# knowles_mic_v2.net
KiCad netlist of a schematic drawn in EAGLE
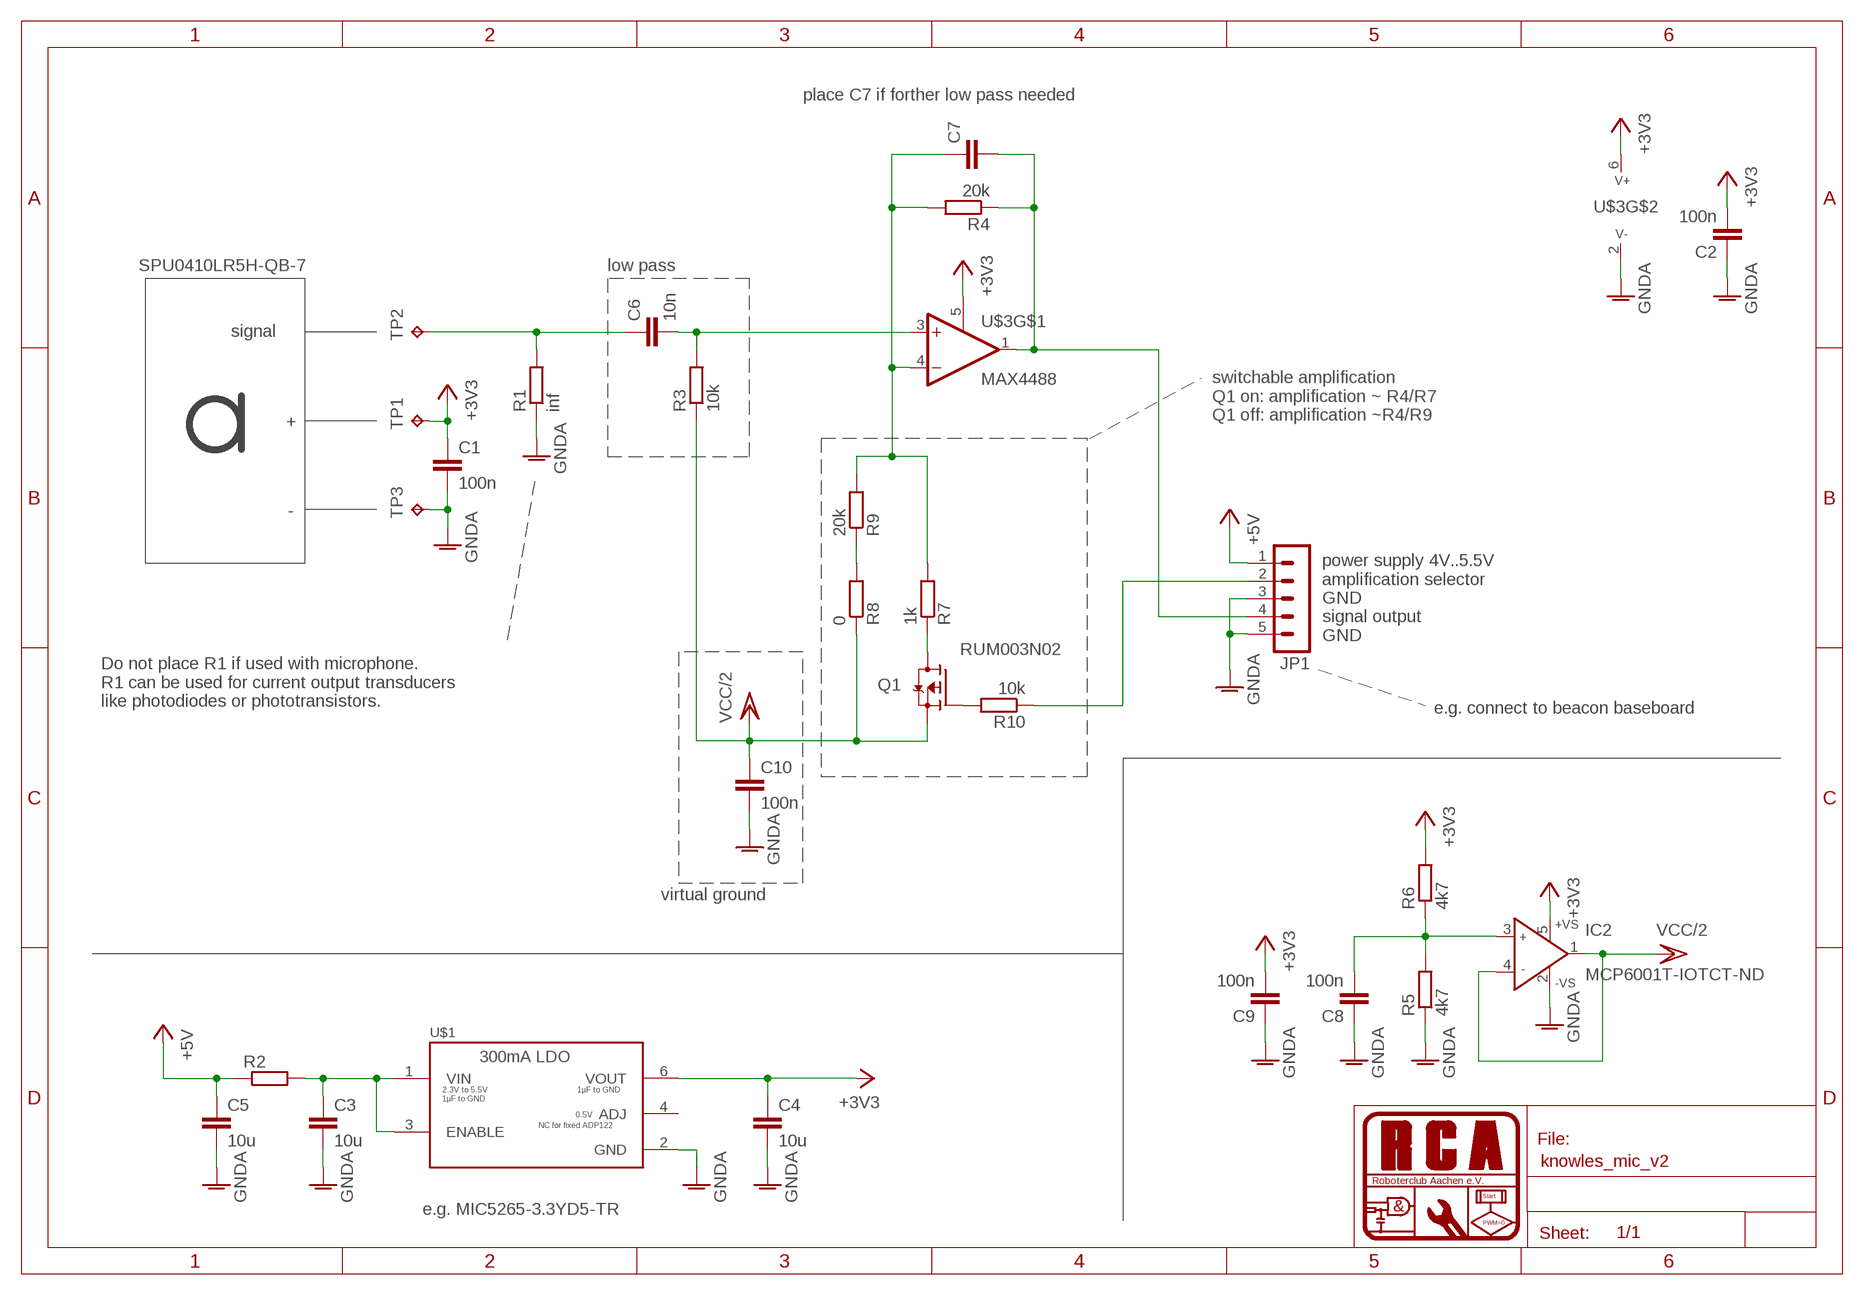
[diagram p0: schematic, sheet 1]

(export (version "E")
  (design (tool "Eeschema 10.0.6"))
  (components
    (comp (ref "C1")
      (value "100n")
      (footprint "eagle-import:C0603")
      (libsource (lib "eagle-import") (part "C-EUC0603"))
    )
    (comp (ref "C2")
      (value "100n")
      (footprint "eagle-import:C0603")
      (libsource (lib "eagle-import") (part "C-EUC0603"))
    )
    (comp (ref "C3")
      (value "10u")
      (footprint "eagle-import:C0805")
      (libsource (lib "eagle-import") (part "C-EUC0805"))
    )
    (comp (ref "C4")
      (value "10u")
      (footprint "eagle-import:C0805")
      (libsource (lib "eagle-import") (part "C-EUC0805"))
    )
    (comp (ref "C5")
      (value "10u")
      (footprint "eagle-import:C0805")
      (libsource (lib "eagle-import") (part "C-EUC0805"))
    )
    (comp (ref "C6")
      (value "10n")
      (footprint "eagle-import:C0603")
      (libsource (lib "eagle-import") (part "C-EUC0603"))
    )
    (comp (ref "C7")
      (value "C-EUC0603")
      (footprint "eagle-import:C0603")
      (libsource (lib "eagle-import") (part "C-EUC0603"))
    )
    (comp (ref "C8")
      (value "100n")
      (footprint "eagle-import:C0603")
      (libsource (lib "eagle-import") (part "C-EUC0603"))
    )
    (comp (ref "C9")
      (value "100n")
      (footprint "eagle-import:C0603")
      (libsource (lib "eagle-import") (part "C-EUC0603"))
    )
    (comp (ref "C10")
      (value "100n")
      (footprint "eagle-import:C0603")
      (libsource (lib "eagle-import") (part "C-EUC0603"))
    )
    (comp (ref "IC2")
      (value "MCP6001T-IOTCT-ND")
      (footprint "eagle-import:SOT23-5")
      (fields (field (name "MF") "ALTERA CORPORATION") (field (name "MPN") "AD8519ARTZ-REEL7"))
      (libsource (lib "eagle-import") (part "AD8519RJ"))
    )
    (comp (ref "JP1")
      (value "PSS_5G")
      (footprint "eagle-import:22-23-2051")
      (libsource (lib "eagle-import") (part "PSS_5G"))
    )
    (comp (ref "Q1")
      (value "RUM003N02")
      (footprint "eagle-import:SC75_INFINEON")
      (libsource (lib "eagle-import") (part "BSA223SP"))
    )
    (comp (ref "R1")
      (value "inf")
      (footprint "eagle-import:R0603")
      (libsource (lib "eagle-import") (part "R-EU_R0603"))
    )
    (comp (ref "R2")
      (value "R-EU_R0603")
      (footprint "eagle-import:R0603")
      (libsource (lib "eagle-import") (part "R-EU_R0603"))
    )
    (comp (ref "R3")
      (value "10k")
      (footprint "eagle-import:R0603")
      (libsource (lib "eagle-import") (part "R-EU_R0603"))
    )
    (comp (ref "R4")
      (value "20k")
      (footprint "eagle-import:R0603")
      (libsource (lib "eagle-import") (part "R-EU_R0603"))
    )
    (comp (ref "R5")
      (value "4k7")
      (footprint "eagle-import:R0603")
      (libsource (lib "eagle-import") (part "R-EU_R0603"))
    )
    (comp (ref "R6")
      (value "4k7")
      (footprint "eagle-import:R0603")
      (libsource (lib "eagle-import") (part "R-EU_R0603"))
    )
    (comp (ref "R7")
      (value "1k")
      (footprint "eagle-import:R0603")
      (libsource (lib "eagle-import") (part "R-EU_R0603"))
    )
    (comp (ref "R8")
      (value "0")
      (footprint "eagle-import:R0603")
      (libsource (lib "eagle-import") (part "R-EU_R0603"))
    )
    (comp (ref "R9")
      (value "20k")
      (footprint "eagle-import:R0603")
      (libsource (lib "eagle-import") (part "R-EU_R0603"))
    )
    (comp (ref "R10")
      (value "10k")
      (footprint "eagle-import:R0603")
      (libsource (lib "eagle-import") (part "R-EU_R0603"))
    )
    (comp (ref "TP1")
      (value "TPTP06R")
      (footprint "eagle-import:TP06R")
      (libsource (lib "eagle-import") (part "TPTP06R"))
    )
    (comp (ref "TP2")
      (value "TPTP06R")
      (footprint "eagle-import:TP06R")
      (libsource (lib "eagle-import") (part "TPTP06R"))
    )
    (comp (ref "TP3")
      (value "TPTP06R")
      (footprint "eagle-import:TP06R")
      (libsource (lib "eagle-import") (part "TPTP06R"))
    )
    (comp (ref "U$1")
      (value "ADP123")
      (footprint "eagle-import:TSOT23-6")
      (libsource (lib "eagle-import") (part "ADP123"))
    )
    (comp (ref "U$3")
      (value "MAX4488")
      (footprint "eagle-import:TSOT23-6")
      (libsource (lib "eagle-import") (part "MAX4488"))
    )
  )
  (nets
    (net (code "1") (name "+3V3") (class "Default")
      (node (ref "C1") (pin "1") (pinfunction "1_1") (pintype "passive"))
      (node (ref "C2") (pin "2") (pinfunction "2_2") (pintype "passive"))
      (node (ref "C4") (pin "1") (pinfunction "1_1") (pintype "passive"))
      (node (ref "C9") (pin "2") (pinfunction "2_2") (pintype "passive"))
      (node (ref "IC2") (pin "5") (pinfunction "+VS_5") (pintype "input"))
      (node (ref "R6") (pin "2") (pinfunction "2_2") (pintype "passive"))
      (node (ref "TP1") (pin "TP") (pinfunction "TP_TP") (pintype "input"))
      (node (ref "U$1") (pin "6") (pinfunction "VOUT_6") (pintype "bidirectional"))
      (node (ref "U$3") (pin "5") (pinfunction "EN_5") (pintype "input"))
      (node (ref "U$3") (pin "6") (pinfunction "V+_6") (pintype "power_in"))
    )
    (net (code "2") (name "+5V") (class "Default")
      (node (ref "C5") (pin "1") (pinfunction "1_1") (pintype "passive"))
      (node (ref "JP1") (pin "1") (pinfunction "1_1") (pintype "passive"))
      (node (ref "R2") (pin "1") (pinfunction "1_1") (pintype "passive"))
    )
    (net (code "3") (name "GNDA") (class "Default")
      (node (ref "C1") (pin "2") (pinfunction "2_2") (pintype "passive"))
      (node (ref "C10") (pin "2") (pinfunction "2_2") (pintype "passive"))
      (node (ref "C2") (pin "1") (pinfunction "1_1") (pintype "passive"))
      (node (ref "C3") (pin "2") (pinfunction "2_2") (pintype "passive"))
      (node (ref "C4") (pin "2") (pinfunction "2_2") (pintype "passive"))
      (node (ref "C5") (pin "2") (pinfunction "2_2") (pintype "passive"))
      (node (ref "C8") (pin "1") (pinfunction "1_1") (pintype "passive"))
      (node (ref "C9") (pin "1") (pinfunction "1_1") (pintype "passive"))
      (node (ref "IC2") (pin "2") (pinfunction "-VS_2") (pintype "input"))
      (node (ref "JP1") (pin "3") (pinfunction "3_3") (pintype "passive"))
      (node (ref "JP1") (pin "5") (pinfunction "5_5") (pintype "passive"))
      (node (ref "R1") (pin "1") (pinfunction "1_1") (pintype "passive"))
      (node (ref "R5") (pin "1") (pinfunction "1_1") (pintype "passive"))
      (node (ref "TP3") (pin "TP") (pinfunction "TP_TP") (pintype "input"))
      (node (ref "U$1") (pin "2") (pinfunction "GND_2") (pintype "bidirectional"))
      (node (ref "U$3") (pin "2") (pinfunction "V-_2") (pintype "power_in"))
    )
    (net (code "4") (name "Net-(C6-Pad1)") (class "Default")
      (node (ref "C6") (pin "1") (pinfunction "1_1") (pintype "passive"))
      (node (ref "R1") (pin "2") (pinfunction "2_2") (pintype "passive"))
      (node (ref "TP2") (pin "TP") (pinfunction "TP_TP") (pintype "input"))
    )
    (net (code "5") (name "Net-(IC2-IN+)") (class "Default")
      (node (ref "C8") (pin "2") (pinfunction "2_2") (pintype "passive"))
      (node (ref "IC2") (pin "3") (pinfunction "IN+_3") (pintype "input"))
      (node (ref "R5") (pin "2") (pinfunction "2_2") (pintype "passive"))
      (node (ref "R6") (pin "1") (pinfunction "1_1") (pintype "passive"))
    )
    (net (code "6") (name "Net-(JP1-Pad2)") (class "Default")
      (node (ref "JP1") (pin "2") (pinfunction "2_2") (pintype "passive"))
      (node (ref "R10") (pin "1") (pinfunction "1_1") (pintype "passive"))
    )
    (net (code "7") (name "Net-(Q1-D)") (class "Default")
      (node (ref "Q1") (pin "2") (pinfunction "D_2") (pintype "passive"))
      (node (ref "R7") (pin "1") (pinfunction "1_1") (pintype "passive"))
    )
    (net (code "8") (name "Net-(Q1-G)") (class "Default")
      (node (ref "Q1") (pin "1") (pinfunction "G_1") (pintype "passive"))
      (node (ref "R10") (pin "2") (pinfunction "2_2") (pintype "passive"))
    )
    (net (code "9") (name "Net-(R8-Pad2)") (class "Default")
      (node (ref "R8") (pin "2") (pinfunction "2_2") (pintype "passive"))
      (node (ref "R9") (pin "1") (pinfunction "1_1") (pintype "passive"))
    )
    (net (code "10") (name "Net-(U$1-ENABLE)") (class "Default")
      (node (ref "C3") (pin "1") (pinfunction "1_1") (pintype "passive"))
      (node (ref "R2") (pin "2") (pinfunction "2_2") (pintype "passive"))
      (node (ref "U$1") (pin "1") (pinfunction "VIN_1") (pintype "bidirectional"))
      (node (ref "U$1") (pin "3") (pinfunction "ENABLE_3") (pintype "bidirectional"))
    )
    (net (code "11") (name "Net-(U$3A-+IN)") (class "Default")
      (node (ref "C6") (pin "2") (pinfunction "2_2") (pintype "passive"))
      (node (ref "R3") (pin "2") (pinfunction "2_2") (pintype "passive"))
      (node (ref "U$3") (pin "3") (pinfunction "+IN_3") (pintype "input"))
    )
    (net (code "12") (name "Net-(U$3A--IN)") (class "Default")
      (node (ref "C7") (pin "1") (pinfunction "1_1") (pintype "passive"))
      (node (ref "R4") (pin "2") (pinfunction "2_2") (pintype "passive"))
      (node (ref "R7") (pin "2") (pinfunction "2_2") (pintype "passive"))
      (node (ref "R9") (pin "2") (pinfunction "2_2") (pintype "passive"))
      (node (ref "U$3") (pin "4") (pinfunction "-IN_4") (pintype "input"))
    )
    (net (code "13") (name "Net-(U$3A-OUT)") (class "Default")
      (node (ref "C7") (pin "2") (pinfunction "2_2") (pintype "passive"))
      (node (ref "JP1") (pin "4") (pinfunction "4_4") (pintype "passive"))
      (node (ref "R4") (pin "1") (pinfunction "1_1") (pintype "passive"))
      (node (ref "U$3") (pin "1") (pinfunction "OUT_1") (pintype "output"))
    )
    (net (code "14") (name "VCC{slash}2") (class "Default")
      (node (ref "C10") (pin "1") (pinfunction "1_1") (pintype "passive"))
      (node (ref "IC2") (pin "1") (pinfunction "OUT_1") (pintype "output"))
      (node (ref "IC2") (pin "4") (pinfunction "IN-_4") (pintype "input"))
      (node (ref "Q1") (pin "3") (pinfunction "S_3") (pintype "passive"))
      (node (ref "R3") (pin "1") (pinfunction "1_1") (pintype "passive"))
      (node (ref "R8") (pin "1") (pinfunction "1_1") (pintype "passive"))
    )
    (net (code "15") (name "unconnected-(U$1-ADJ-Pad4)") (class "Default")
      (node (ref "U$1") (pin "4") (pinfunction "ADJ_4") (pintype "bidirectional"))
    )
  )
)
